# USB_TypeC.net
KiCad netlist of a schematic drawn in Altium Designer
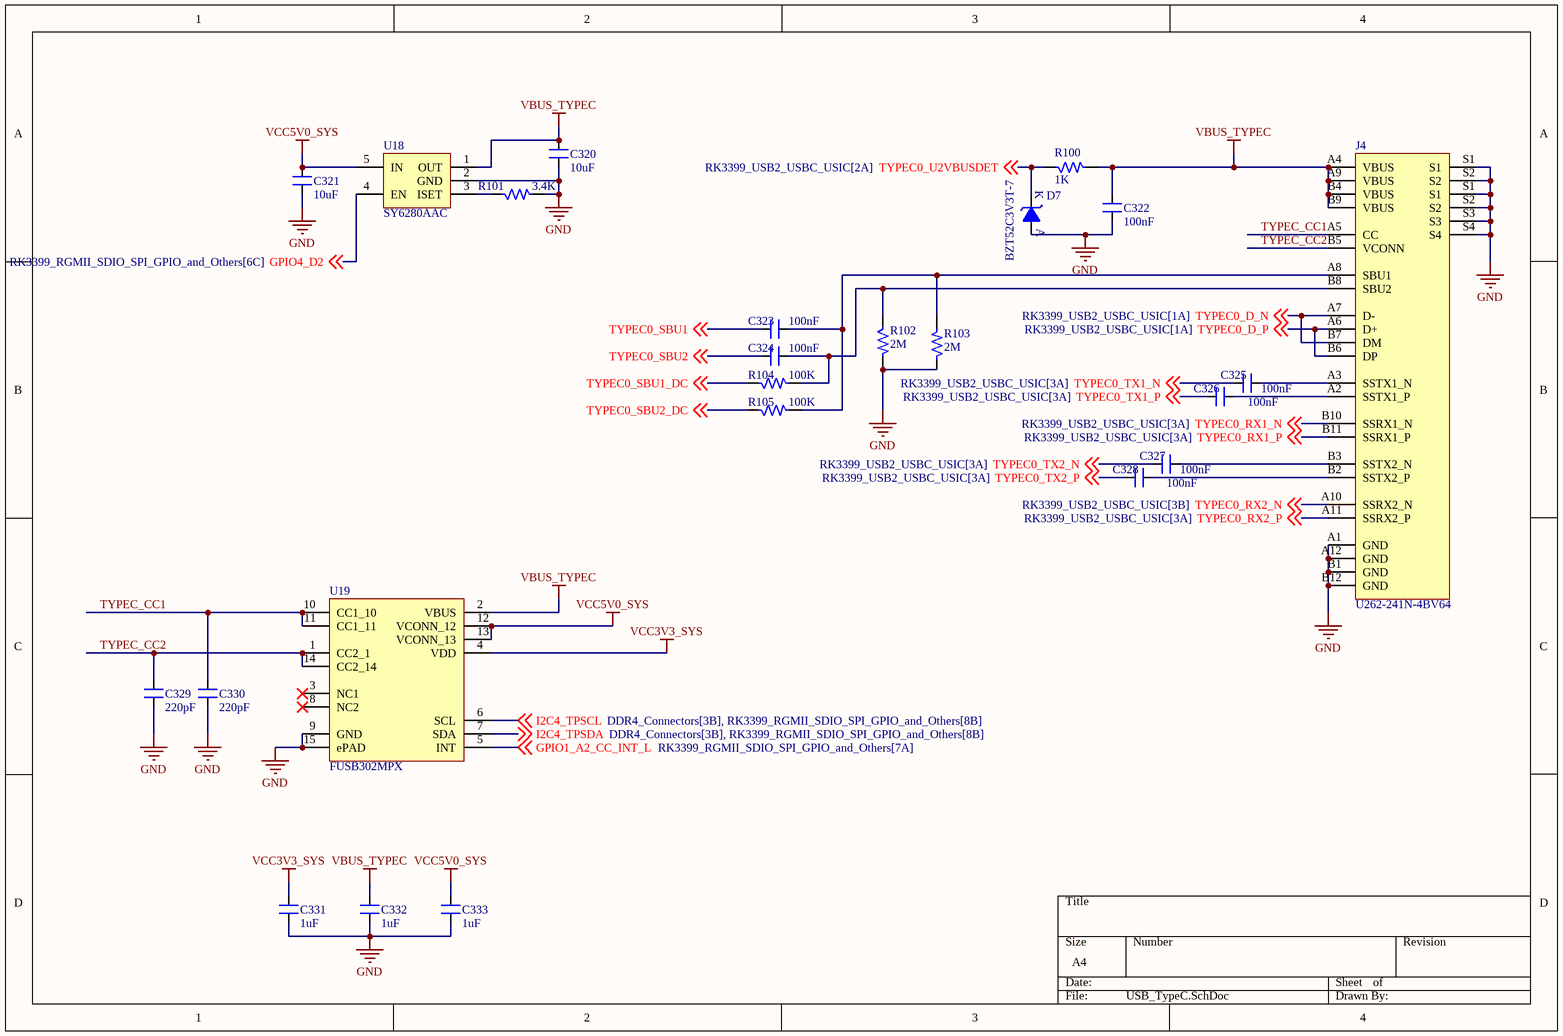
[diagram p0: USB_TypeC.SchDoc]

(export (version "E")
  (design (tool "Eeschema 10.0.6"))
  (components
    (comp (ref "C320")
      (value "10uF")
      (footprint "CAP_0402")
      (description "10µF ±20% 10V Ceramic Capacitor X5R 0402 (1005 Metric)")
      (fields
        (field (name "MANUFACTURER PART NUMBER") "CL05A106MP5NUNC")
        (field (name "MANUFACTURER") "Samsung Electro-Mechanics")
      )
      (libsource (lib "EsteemPCB_SOM_Course_schlib") (part "CAP_10uF-10V-20%-0402"))
    )
    (comp (ref "C321")
      (value "10uF")
      (footprint "CAP_0402")
      (description "10µF ±20% 10V Ceramic Capacitor X5R 0402 (1005 Metric)")
      (fields
        (field (name "MANUFACTURER PART NUMBER") "CL05A106MP5NUNC")
        (field (name "MANUFACTURER") "Samsung Electro-Mechanics")
      )
      (libsource (lib "EsteemPCB_SOM_Course_schlib") (part "CAP_10uF-10V-20%-0402"))
    )
    (comp (ref "C322")
      (value "100nF")
      (footprint "CAP_0603")
      (description "0.1µF ±10% 10V Ceramic Capacitor X7R 0603 (1608 Metric)")
      (fields
        (field (name "MANUFACTURER") "Yageo")
        (field (name "MANUFACTURER PART NUMBER") "CC0603KRX7R6BB104")
      )
      (libsource (lib "EsteemPCB_SOM_Course_schlib") (part "CAP_100nF-10V-5%-0603"))
    )
    (comp (ref "C323")
      (value "100nF")
      (footprint "CAP_0603")
      (description "0.1µF ±10% 10V Ceramic Capacitor X7R 0603 (1608 Metric)")
      (fields
        (field (name "MANUFACTURER") "Yageo")
        (field (name "MANUFACTURER PART NUMBER") "CC0603KRX7R6BB104")
      )
      (libsource (lib "EsteemPCB_SOM_Course_schlib") (part "CAP_100nF-10V-5%-0603"))
    )
    (comp (ref "C324")
      (value "100nF")
      (footprint "CAP_0603")
      (description "0.1µF ±10% 10V Ceramic Capacitor X7R 0603 (1608 Metric)")
      (fields
        (field (name "MANUFACTURER") "Yageo")
        (field (name "MANUFACTURER PART NUMBER") "CC0603KRX7R6BB104")
      )
      (libsource (lib "EsteemPCB_SOM_Course_schlib") (part "CAP_100nF-10V-5%-0603"))
    )
    (comp (ref "C325")
      (value "100nF")
      (footprint "CAP_0603")
      (description "0.1µF ±10% 10V Ceramic Capacitor X7R 0603 (1608 Metric)")
      (fields
        (field (name "MANUFACTURER") "Yageo")
        (field (name "MANUFACTURER PART NUMBER") "CC0603KRX7R6BB104")
      )
      (libsource (lib "EsteemPCB_SOM_Course_schlib") (part "CAP_100nF-10V-5%-0603"))
    )
    (comp (ref "C326")
      (value "100nF")
      (footprint "CAP_0603")
      (description "0.1µF ±10% 10V Ceramic Capacitor X7R 0603 (1608 Metric)")
      (fields
        (field (name "MANUFACTURER") "Yageo")
        (field (name "MANUFACTURER PART NUMBER") "CC0603KRX7R6BB104")
      )
      (libsource (lib "EsteemPCB_SOM_Course_schlib") (part "CAP_100nF-10V-5%-0603"))
    )
    (comp (ref "C327")
      (value "100nF")
      (footprint "CAP_0603")
      (description "0.1µF ±10% 10V Ceramic Capacitor X7R 0603 (1608 Metric)")
      (fields
        (field (name "MANUFACTURER") "Yageo")
        (field (name "MANUFACTURER PART NUMBER") "CC0603KRX7R6BB104")
      )
      (libsource (lib "EsteemPCB_SOM_Course_schlib") (part "CAP_100nF-10V-5%-0603"))
    )
    (comp (ref "C328")
      (value "100nF")
      (footprint "CAP_0603")
      (description "0.1µF ±10% 10V Ceramic Capacitor X7R 0603 (1608 Metric)")
      (fields
        (field (name "MANUFACTURER") "Yageo")
        (field (name "MANUFACTURER PART NUMBER") "CC0603KRX7R6BB104")
      )
      (libsource (lib "EsteemPCB_SOM_Course_schlib") (part "CAP_100nF-10V-5%-0603"))
    )
    (comp (ref "C329")
      (value "220pF")
      (footprint "CAP_0402")
      (description "220pF ±10% 10V Ceramic Capacitor X7R 0402 (1005 Metric)")
      (fields
        (field (name "MANUFACTURER") "KEMET")
        (field (name "MANUFACTURER PART NUMBER") "C0402C221K8RAC7867")
      )
      (libsource (lib "EsteemPCB_SOM_Course_schlib") (part "CAP_220pF-10V-10%-0402"))
    )
    (comp (ref "C330")
      (value "220pF")
      (footprint "CAP_0402")
      (description "220pF ±10% 10V Ceramic Capacitor X7R 0402 (1005 Metric)")
      (fields
        (field (name "MANUFACTURER") "KEMET")
        (field (name "MANUFACTURER PART NUMBER") "C0402C221K8RAC7867")
      )
      (libsource (lib "EsteemPCB_SOM_Course_schlib") (part "CAP_220pF-10V-10%-0402"))
    )
    (comp (ref "C331")
      (value "1uF")
      (footprint "CAP_0402")
      (description "1µF ±10% 10V Ceramic Capacitor X6S 0402 (1005 Metric)")
      (fields
        (field (name "MANUFACTURER") "Murata Electronics")
        (field (name "MANUFACTURER PART NUMBER") "GRT155C81A105KE01D")
      )
      (libsource (lib "EsteemPCB_SOM_Course_schlib") (part "CAP_1uF-10V-10%-0402"))
    )
    (comp (ref "C332")
      (value "1uF")
      (footprint "CAP_0402")
      (description "1µF ±10% 10V Ceramic Capacitor X6S 0402 (1005 Metric)")
      (fields
        (field (name "MANUFACTURER") "Murata Electronics")
        (field (name "MANUFACTURER PART NUMBER") "GRT155C81A105KE01D")
      )
      (libsource (lib "EsteemPCB_SOM_Course_schlib") (part "CAP_1uF-10V-10%-0402"))
    )
    (comp (ref "C333")
      (value "1uF")
      (footprint "CAP_0402")
      (description "1µF ±10% 10V Ceramic Capacitor X6S 0402 (1005 Metric)")
      (fields
        (field (name "MANUFACTURER") "Murata Electronics")
        (field (name "MANUFACTURER PART NUMBER") "GRT155C81A105KE01D")
      )
      (libsource (lib "EsteemPCB_SOM_Course_schlib") (part "CAP_1uF-10V-10%-0402"))
    )
    (comp (ref "D7")
      (value "BZT52C3V3T-7")
      (footprint "DIO_SOD523")
      (description "Zener Diode 3.3V 300mW ±6% Surface Mount SOD-523")
      (fields (field (name "MANUFACTURER") "Diodes Incorporated"))
      (libsource (lib "EsteemPCB_SOM_Course_schlib") (part "DIO-Z_3.3V-300mW-SOD-523"))
    )
    (comp (ref "J4")
      (value "U262-241N-4BV64")
      (footprint "CON24_19.64_U262-241N-4BV64_TH_RA")
      (description "USB - Type C Female 24 SMD USB Connectors RoHS")
      (fields (field (name "MANUFACTURER") "XKB Connectivity"))
      (libsource (lib "EsteemPCB_SOM_Course_schlib") (part "CON-TYPEC_U262-241N-4BV64-SMD"))
    )
    (comp (ref "R100")
      (value "1K")
      (footprint "RES_0402")
      (description "1 kOhms ±1% 0.1W, 1/10W Chip Resistor 0402 (1005 Metric) Anti-Sulfur Thin Film")
      (fields
        (field (name "MANUFACTURER") "Vishay Beyschlag/Draloric/BC Components")
        (field (name "MANUFACTURER PART NUMBER") "MCS04020C1001FE000")
      )
      (libsource (lib "EsteemPCB_SOM_Course_schlib") (part "RES_1K-0.1W-1%-0402"))
    )
    (comp (ref "R101")
      (value "3.4K")
      (footprint "RES_0402")
      (description "3.4 kOhms ±1% 0.1W, 1/10W Chip Resistor 0402 (1005 Metric) Automotive AEC-Q200 Thick Film")
      (fields
        (field (name "MANUFACTURER") "Panasonic Electronic Components")
        (field (name "MANUFACTURER PART NUMBER") "ERJ-2RKF3401X")
      )
      (libsource (lib "EsteemPCB_SOM_Course_schlib") (part "RES_3.4K-0.1W-1%-0402"))
    )
    (comp (ref "R102")
      (value "2M")
      (footprint "RES_0402")
      (description "2 MOhms ±1% 0.1W, 1/10W Chip Resistor 0402 (1005 Metric) Anti-Sulfur Thin Film")
      (fields
        (field (name "MANUFACTURER") "Vishay Beyschlag/Draloric/BC Components")
        (field (name "MANUFACTURER PART NUMBER") "MCS04020C2004FE000")
      )
      (libsource (lib "EsteemPCB_SOM_Course_schlib") (part "RES_2M-0.1W-1%-0402"))
    )
    (comp (ref "R103")
      (value "2M")
      (footprint "RES_0402")
      (description "2 MOhms ±1% 0.1W, 1/10W Chip Resistor 0402 (1005 Metric) Anti-Sulfur Thin Film")
      (fields
        (field (name "MANUFACTURER") "Vishay Beyschlag/Draloric/BC Components")
        (field (name "MANUFACTURER PART NUMBER") "MCS04020C2004FE000")
      )
      (libsource (lib "EsteemPCB_SOM_Course_schlib") (part "RES_2M-0.1W-1%-0402"))
    )
    (comp (ref "R104")
      (value "100K")
      (footprint "RES_0402")
      (description "100 kOhms ±1% 0.1W, 1/10W Chip Resistor 0402 (1005 Metric) Anti-Sulfur Thin Film")
      (fields
        (field (name "MANUFACTURER") "Vishay Beyschlag/Draloric/BC Components")
        (field (name "MANUFACTURER PART NUMBER") "MCS04020C1003FE000")
      )
      (libsource (lib "EsteemPCB_SOM_Course_schlib") (part "RES_100K-0.1W-1%-0402"))
    )
    (comp (ref "R105")
      (value "100K")
      (footprint "RES_0402")
      (description "100 kOhms ±1% 0.1W, 1/10W Chip Resistor 0402 (1005 Metric) Anti-Sulfur Thin Film")
      (fields
        (field (name "MANUFACTURER") "Vishay Beyschlag/Draloric/BC Components")
        (field (name "MANUFACTURER PART NUMBER") "MCS04020C1003FE000")
      )
      (libsource (lib "EsteemPCB_SOM_Course_schlib") (part "RES_100K-0.1W-1%-0402"))
    )
    (comp (ref "U18")
      (value "SY6280AAC")
      (footprint "SOT23-5")
      (description "SOT-23-5 PMIC - Power Distribution Switches RoHS")
      (fields (field (name "MANUFACTURER") "Silergy Corp"))
      (libsource (lib "EsteemPCB_SOM_Course_schlib") (part "REG-ADJ_5.5V-5.5V-1.25A-SOT-23-5"))
    )
    (comp (ref "U19")
      (value "FUSB302MPX")
      (footprint "MLP-14_98.4X98.4_SMD")
      (description "USB Controller USB 3.1 USB Interface 14-MLP (2.5x2.5)")
      (fields (field (name "MANUFACTURER") "ON Semiconductor"))
      (libsource (lib "EsteemPCB_SOM_Course_schlib") (part "IC_FUSB302MPX"))
    )
  )
  (nets
    (net (code "1") (name "/TYPEC_CC1") (class "Default")
      (node (ref "C330") (pin "2") (pinfunction "2_2") (pintype "passive"))
      (node (ref "J4") (pin "A5") (pinfunction "CC_A5") (pintype "passive"))
      (node (ref "U19") (pin "10") (pinfunction "CC1_10_10") (pintype "passive"))
      (node (ref "U19") (pin "11") (pinfunction "CC1_11_11") (pintype "passive"))
    )
    (net (code "2") (name "/TYPEC_CC2") (class "Default")
      (node (ref "C329") (pin "2") (pinfunction "2_2") (pintype "passive"))
      (node (ref "J4") (pin "B5") (pinfunction "VCONN_B5") (pintype "passive"))
      (node (ref "U19") (pin "1") (pinfunction "CC2_1_1") (pintype "passive"))
      (node (ref "U19") (pin "14") (pinfunction "CC2_14_14") (pintype "passive"))
    )
    (net (code "3") (name "GND") (class "Default")
      (node (ref "C320") (pin "1") (pinfunction "1_1") (pintype "passive"))
      (node (ref "C321") (pin "1") (pinfunction "1_1") (pintype "passive"))
      (node (ref "C322") (pin "1") (pinfunction "1_1") (pintype "passive"))
      (node (ref "C329") (pin "1") (pinfunction "1_1") (pintype "passive"))
      (node (ref "C330") (pin "1") (pinfunction "1_1") (pintype "passive"))
      (node (ref "C331") (pin "1") (pinfunction "1_1") (pintype "passive"))
      (node (ref "C332") (pin "1") (pinfunction "1_1") (pintype "passive"))
      (node (ref "C333") (pin "1") (pinfunction "1_1") (pintype "passive"))
      (node (ref "D7") (pin "A") (pinfunction "A_A") (pintype "passive"))
      (node (ref "J4") (pin "A1") (pinfunction "GND_A1") (pintype "passive"))
      (node (ref "J4") (pin "A12") (pinfunction "GND_A12") (pintype "passive"))
      (node (ref "J4") (pin "B1") (pinfunction "GND_B1") (pintype "passive"))
      (node (ref "J4") (pin "B12") (pinfunction "GND_B12") (pintype "passive"))
      (node (ref "J4") (pin "S1") (pinfunction "S1_S1") (pintype "passive"))
      (node (ref "J4") (pin "S2") (pinfunction "S2_S2") (pintype "passive"))
      (node (ref "J4") (pin "S3") (pinfunction "S3_S3") (pintype "passive"))
      (node (ref "J4") (pin "S4") (pinfunction "S4_S4") (pintype "passive"))
      (node (ref "R101") (pin "2") (pinfunction "2_2") (pintype "passive"))
      (node (ref "R102") (pin "2") (pinfunction "2_2") (pintype "passive"))
      (node (ref "R103") (pin "1") (pinfunction "1_1") (pintype "passive"))
      (node (ref "U18") (pin "2") (pinfunction "GND_2") (pintype "passive"))
      (node (ref "U19") (pin "15") (pinfunction "ePAD_15") (pintype "passive"))
      (node (ref "U19") (pin "9") (pinfunction "GND_9") (pintype "passive"))
    )
    (net (code "4") (name "GPIO1_A2_CC_INT_L") (class "Default")
      (node (ref "U19") (pin "5") (pinfunction "INT_5") (pintype "passive"))
    )
    (net (code "5") (name "GPIO4_D2") (class "Default")
      (node (ref "U18") (pin "4") (pinfunction "EN_4") (pintype "passive"))
    )
    (net (code "6") (name "I2C4_TPSCL") (class "Default")
      (node (ref "U19") (pin "6") (pinfunction "SCL_6") (pintype "passive"))
    )
    (net (code "7") (name "I2C4_TPSDA") (class "Default")
      (node (ref "U19") (pin "7") (pinfunction "SDA_7") (pintype "passive"))
    )
    (net (code "8") (name "Net-(J4-SBU1)") (class "Default")
      (node (ref "C323") (pin "1") (pinfunction "1_1") (pintype "passive"))
      (node (ref "J4") (pin "A8") (pinfunction "SBU1_A8") (pintype "passive"))
      (node (ref "R103") (pin "2") (pinfunction "2_2") (pintype "passive"))
      (node (ref "R105") (pin "2") (pinfunction "2_2") (pintype "passive"))
    )
    (net (code "9") (name "Net-(J4-SBU2)") (class "Default")
      (node (ref "C324") (pin "1") (pinfunction "1_1") (pintype "passive"))
      (node (ref "J4") (pin "B8") (pinfunction "SBU2_B8") (pintype "passive"))
      (node (ref "R102") (pin "1") (pinfunction "1_1") (pintype "passive"))
      (node (ref "R104") (pin "2") (pinfunction "2_2") (pintype "passive"))
    )
    (net (code "10") (name "Net-(J4-SSTX1_N)") (class "Default")
      (node (ref "C325") (pin "1") (pinfunction "1_1") (pintype "passive"))
      (node (ref "J4") (pin "A3") (pinfunction "SSTX1_N_A3") (pintype "passive"))
    )
    (net (code "11") (name "Net-(J4-SSTX1_P)") (class "Default")
      (node (ref "C326") (pin "1") (pinfunction "1_1") (pintype "passive"))
      (node (ref "J4") (pin "A2") (pinfunction "SSTX1_P_A2") (pintype "passive"))
    )
    (net (code "12") (name "Net-(J4-SSTX2_N)") (class "Default")
      (node (ref "C327") (pin "1") (pinfunction "1_1") (pintype "passive"))
      (node (ref "J4") (pin "B3") (pinfunction "SSTX2_N_B3") (pintype "passive"))
    )
    (net (code "13") (name "Net-(J4-SSTX2_P)") (class "Default")
      (node (ref "C328") (pin "1") (pinfunction "1_1") (pintype "passive"))
      (node (ref "J4") (pin "B2") (pinfunction "SSTX2_P_B2") (pintype "passive"))
    )
    (net (code "14") (name "Net-(U18-ISET)") (class "Default")
      (node (ref "R101") (pin "1") (pinfunction "1_1") (pintype "passive"))
      (node (ref "U18") (pin "3") (pinfunction "ISET_3") (pintype "passive"))
    )
    (net (code "15") (name "TYPEC0_D_N") (class "Default")
      (node (ref "J4") (pin "A7") (pinfunction "D-_A7") (pintype "passive"))
      (node (ref "J4") (pin "B7") (pinfunction "DM_B7") (pintype "passive"))
    )
    (net (code "16") (name "TYPEC0_D_P") (class "Default")
      (node (ref "J4") (pin "A6") (pinfunction "D+_A6") (pintype "passive"))
      (node (ref "J4") (pin "B6") (pinfunction "DP_B6") (pintype "passive"))
    )
    (net (code "17") (name "TYPEC0_RX1_N") (class "Default")
      (node (ref "J4") (pin "B10") (pinfunction "SSRX1_N_B10") (pintype "passive"))
    )
    (net (code "18") (name "TYPEC0_RX1_P") (class "Default")
      (node (ref "J4") (pin "B11") (pinfunction "SSRX1_P_B11") (pintype "passive"))
    )
    (net (code "19") (name "TYPEC0_RX2_N") (class "Default")
      (node (ref "J4") (pin "A10") (pinfunction "SSRX2_N_A10") (pintype "passive"))
    )
    (net (code "20") (name "TYPEC0_RX2_P") (class "Default")
      (node (ref "J4") (pin "A11") (pinfunction "SSRX2_P_A11") (pintype "passive"))
    )
    (net (code "21") (name "TYPEC0_SBU1") (class "Default")
      (node (ref "C323") (pin "2") (pinfunction "2_2") (pintype "passive"))
    )
    (net (code "22") (name "TYPEC0_SBU1_DC") (class "Default")
      (node (ref "R104") (pin "1") (pinfunction "1_1") (pintype "passive"))
    )
    (net (code "23") (name "TYPEC0_SBU2") (class "Default")
      (node (ref "C324") (pin "2") (pinfunction "2_2") (pintype "passive"))
    )
    (net (code "24") (name "TYPEC0_SBU2_DC") (class "Default")
      (node (ref "R105") (pin "1") (pinfunction "1_1") (pintype "passive"))
    )
    (net (code "25") (name "TYPEC0_TX1_N") (class "Default")
      (node (ref "C325") (pin "2") (pinfunction "2_2") (pintype "passive"))
    )
    (net (code "26") (name "TYPEC0_TX1_P") (class "Default")
      (node (ref "C326") (pin "2") (pinfunction "2_2") (pintype "passive"))
    )
    (net (code "27") (name "TYPEC0_TX2_N") (class "Default")
      (node (ref "C327") (pin "2") (pinfunction "2_2") (pintype "passive"))
    )
    (net (code "28") (name "TYPEC0_TX2_P") (class "Default")
      (node (ref "C328") (pin "2") (pinfunction "2_2") (pintype "passive"))
    )
    (net (code "29") (name "TYPEC0_U2VBUSDET") (class "Default")
      (node (ref "D7") (pin "K") (pinfunction "K_K") (pintype "passive"))
      (node (ref "R100") (pin "1") (pinfunction "1_1") (pintype "passive"))
    )
    (net (code "30") (name "VBUS_TYPEC") (class "Default")
      (node (ref "C320") (pin "2") (pinfunction "2_2") (pintype "passive"))
      (node (ref "C322") (pin "2") (pinfunction "2_2") (pintype "passive"))
      (node (ref "C332") (pin "2") (pinfunction "2_2") (pintype "passive"))
      (node (ref "J4") (pin "A4") (pinfunction "VBUS_A4") (pintype "passive"))
      (node (ref "J4") (pin "A9") (pinfunction "VBUS_A9") (pintype "passive"))
      (node (ref "J4") (pin "B4") (pinfunction "VBUS_B4") (pintype "passive"))
      (node (ref "J4") (pin "B9") (pinfunction "VBUS_B9") (pintype "passive"))
      (node (ref "R100") (pin "2") (pinfunction "2_2") (pintype "passive"))
      (node (ref "U18") (pin "1") (pinfunction "OUT_1") (pintype "passive"))
      (node (ref "U19") (pin "2") (pinfunction "VBUS_2") (pintype "passive"))
    )
    (net (code "31") (name "VCC3V3_SYS") (class "Default")
      (node (ref "C331") (pin "2") (pinfunction "2_2") (pintype "passive"))
      (node (ref "U19") (pin "4") (pinfunction "VDD_4") (pintype "passive"))
    )
    (net (code "32") (name "VCC5V0_SYS") (class "Default")
      (node (ref "C321") (pin "2") (pinfunction "2_2") (pintype "passive"))
      (node (ref "C333") (pin "2") (pinfunction "2_2") (pintype "passive"))
      (node (ref "U18") (pin "5") (pinfunction "IN_5") (pintype "passive"))
      (node (ref "U19") (pin "12") (pinfunction "VCONN_12_12") (pintype "passive"))
      (node (ref "U19") (pin "13") (pinfunction "VCONN_13_13") (pintype "passive"))
    )
    (net (code "33") (name "unconnected-(U19-NC1-Pad3)") (class "Default")
      (node (ref "U19") (pin "3") (pinfunction "NC1_3") (pintype "passive+no_connect"))
    )
    (net (code "34") (name "unconnected-(U19-NC2-Pad8)") (class "Default")
      (node (ref "U19") (pin "8") (pinfunction "NC2_8") (pintype "passive+no_connect"))
    )
  )
)
